# mainBoard.net
KiCad netlist of a schematic drawn in EAGLE
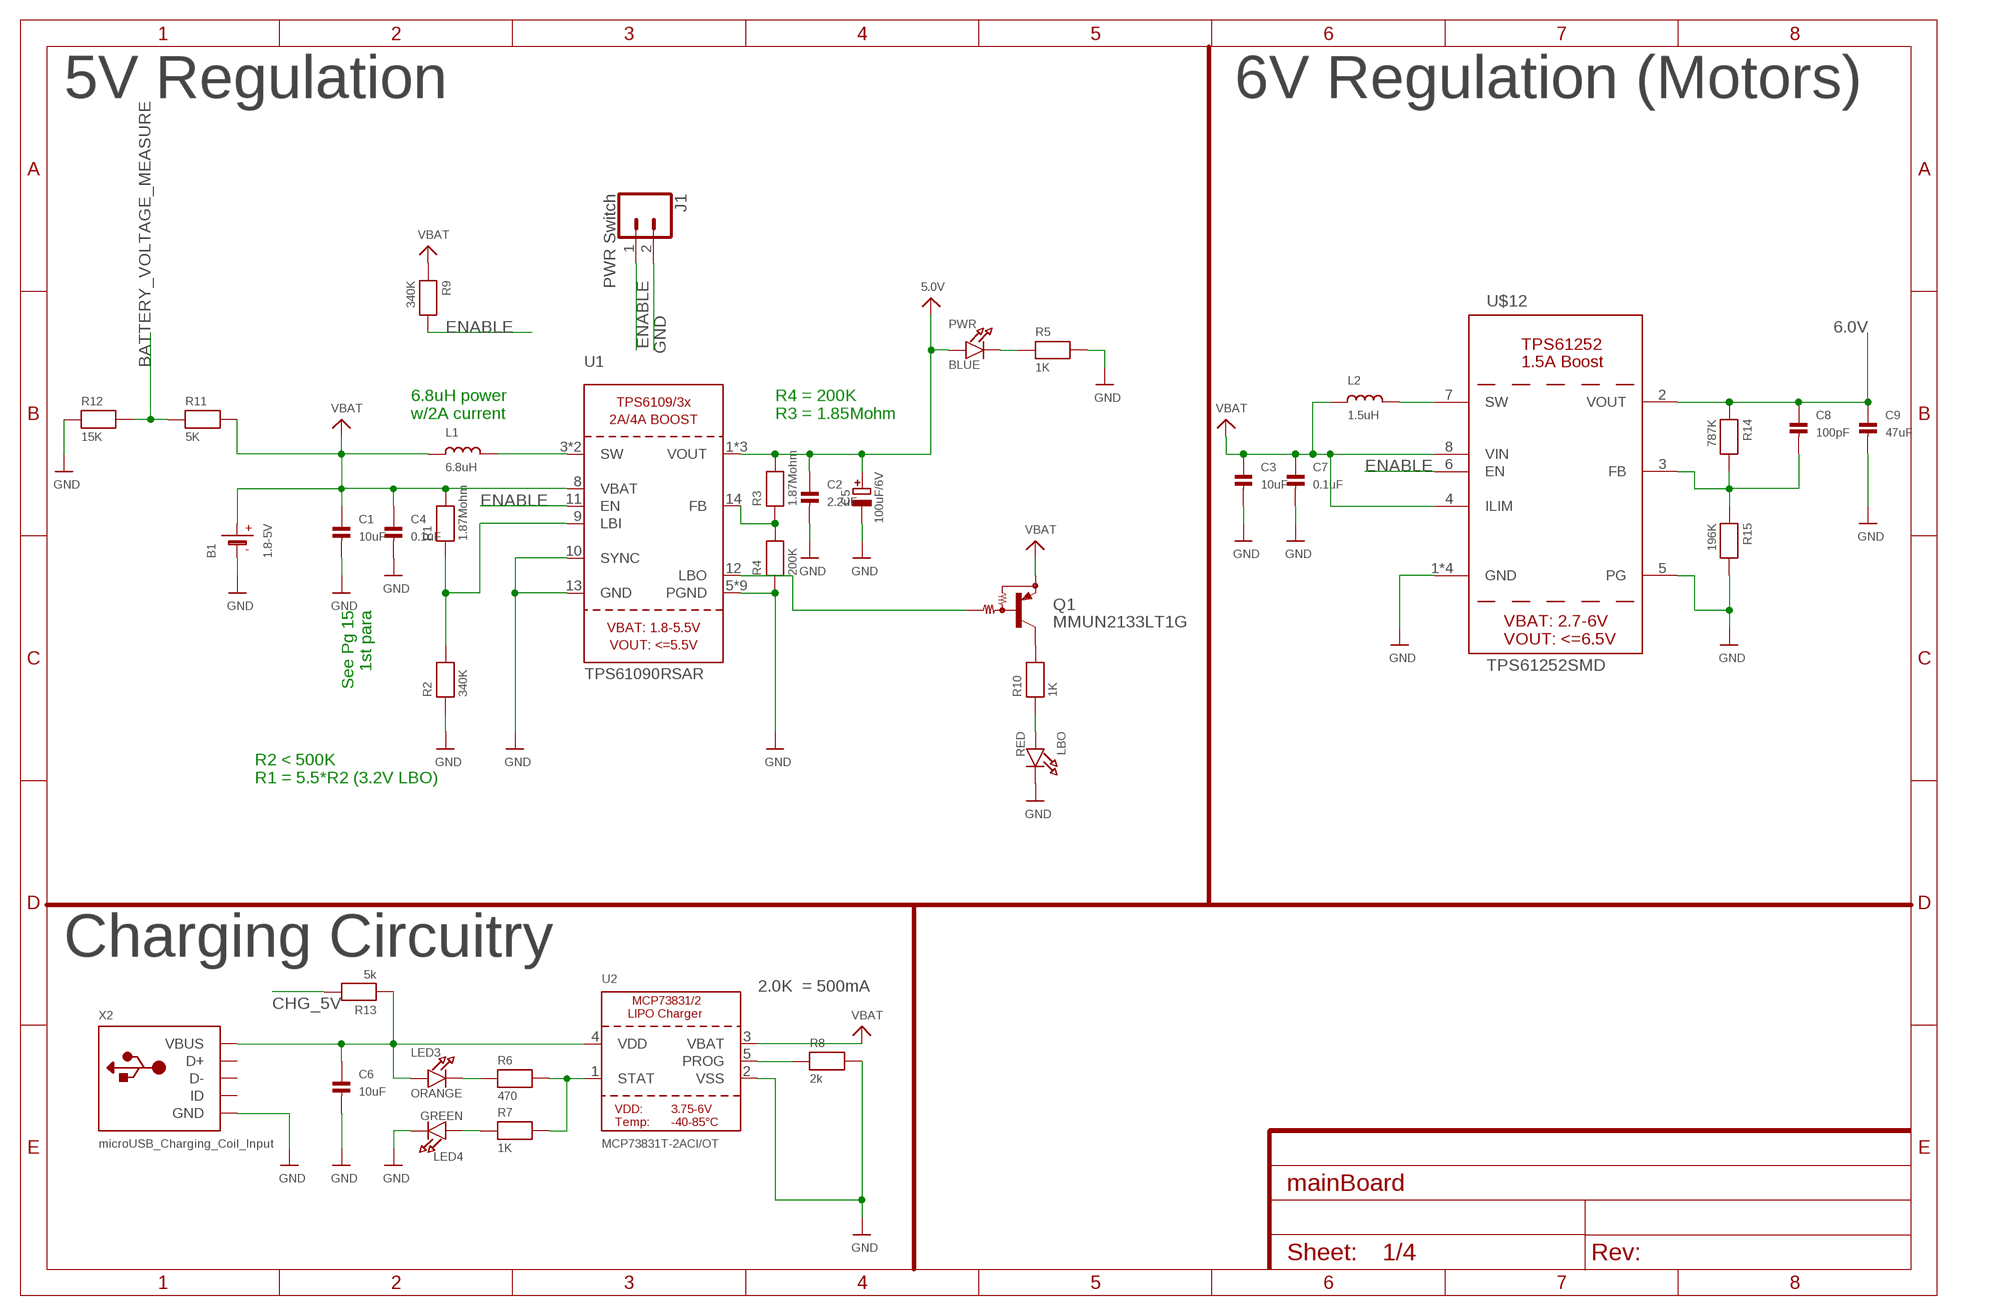
[diagram p0: schematic, sheet 1]
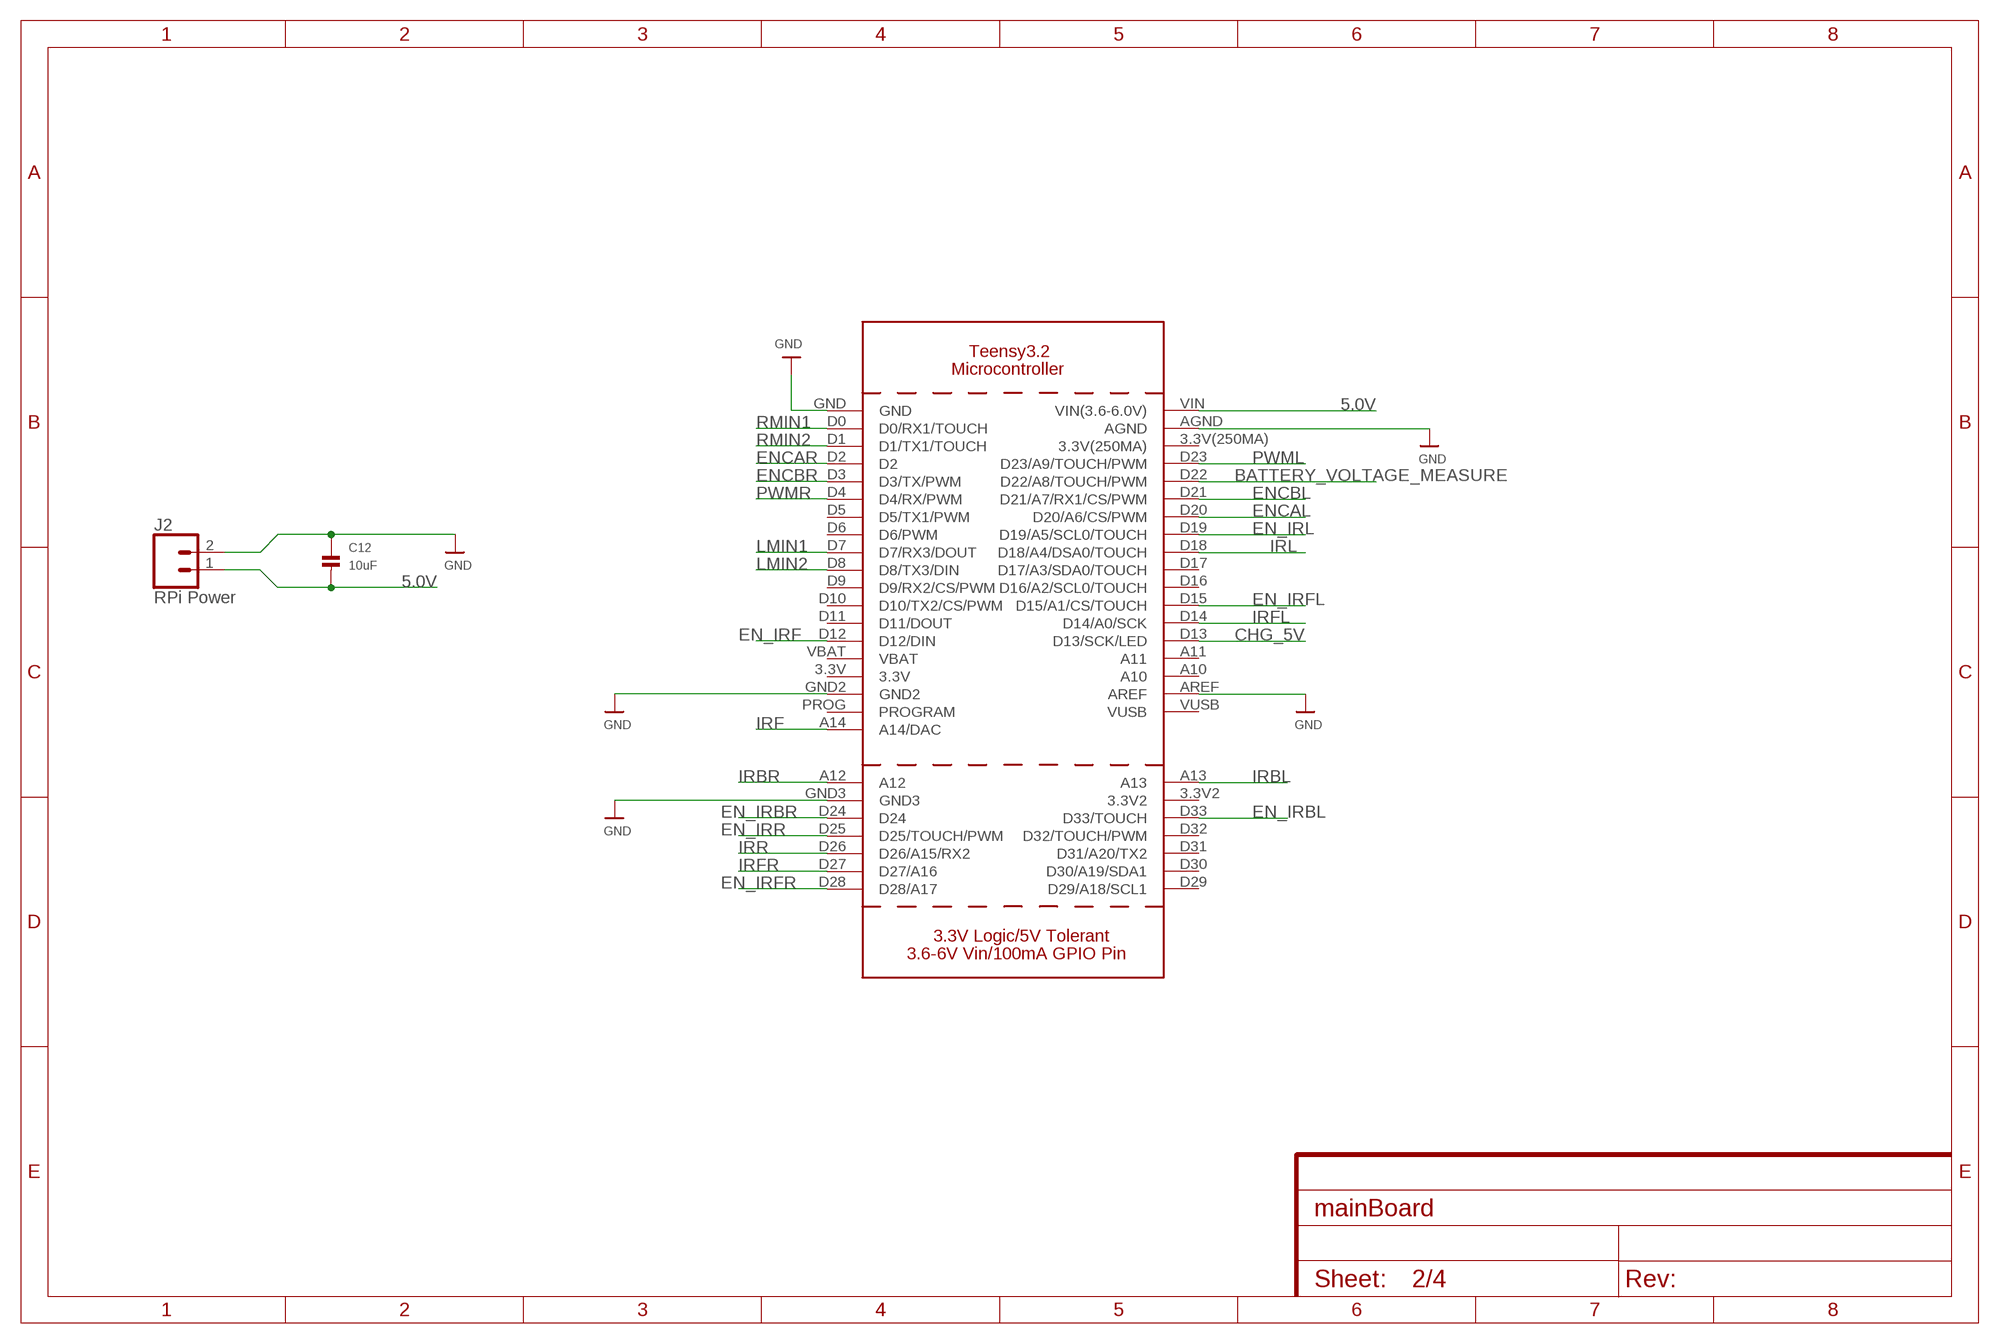
[diagram p1: schematic, sheet 2]
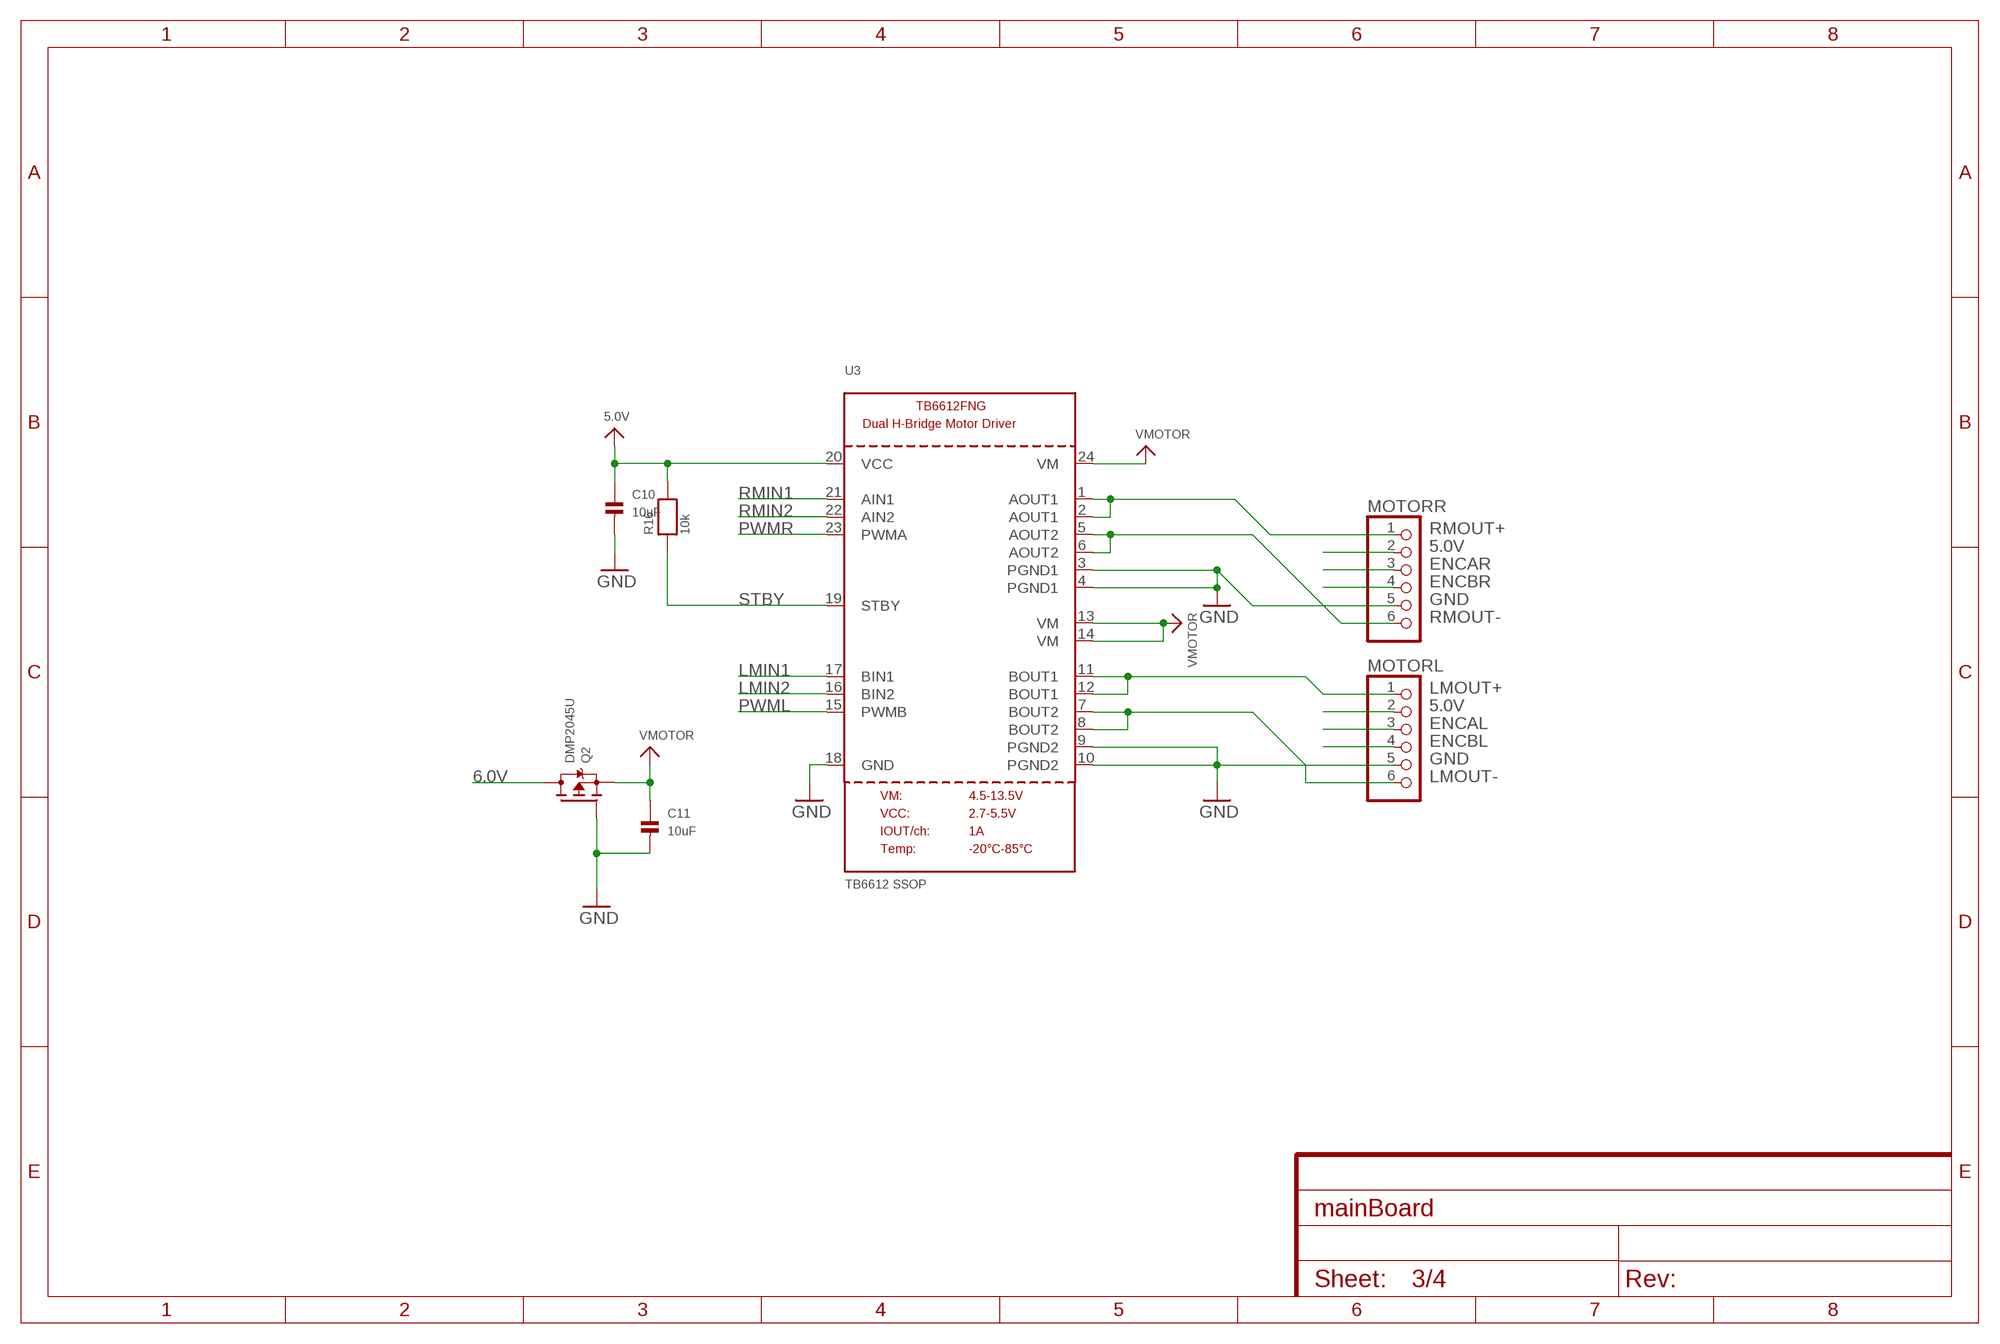
[diagram p2: schematic, sheet 3]
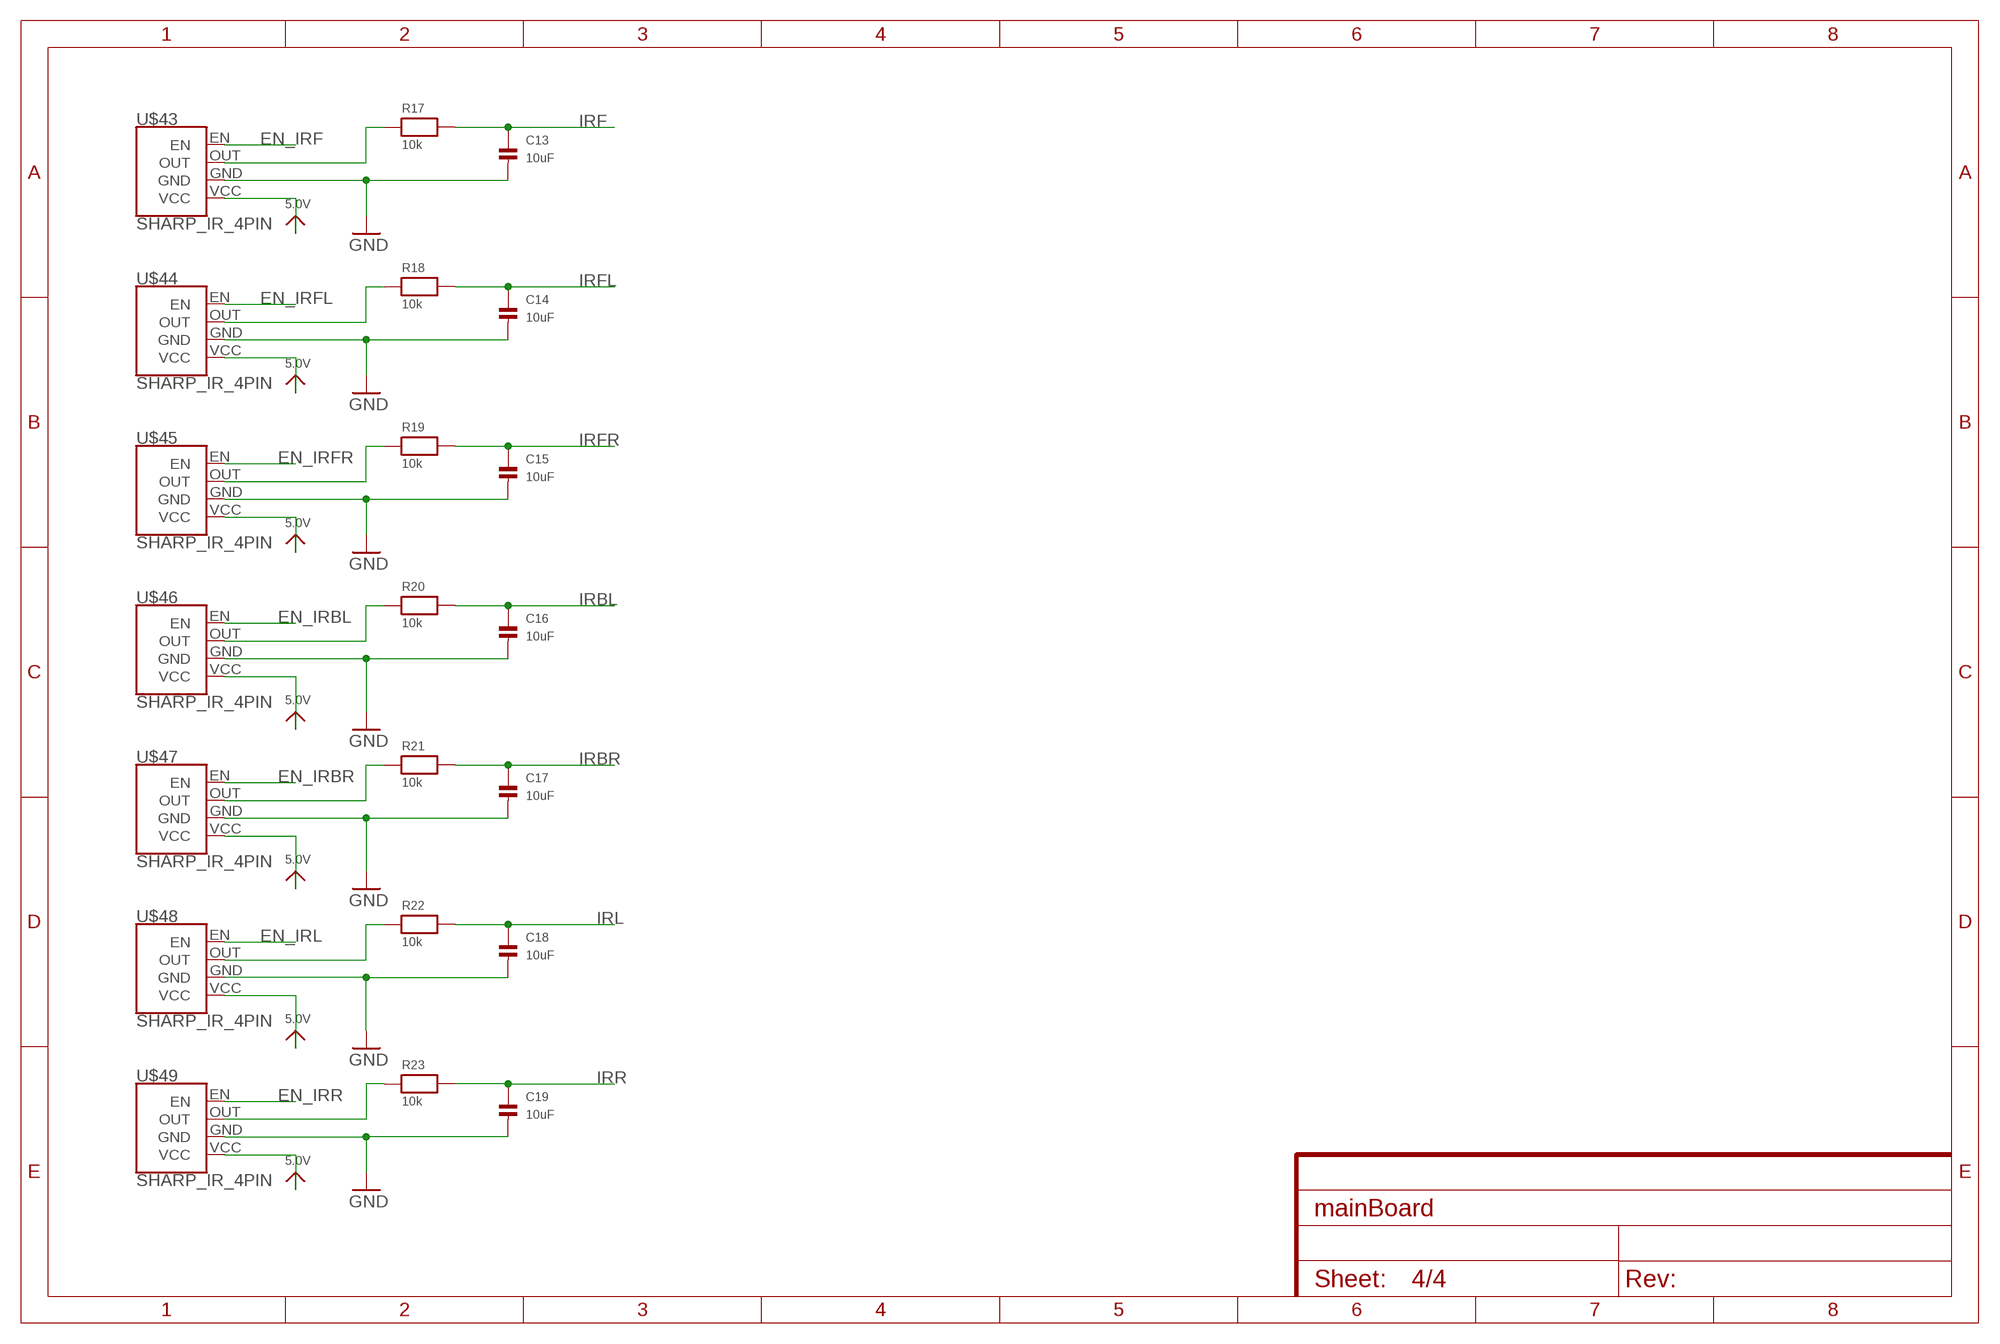
[diagram p3: schematic, sheet 4]

(export (version "E")
  (design (tool "Eeschema 10.0.6"))
  (components
    (comp (ref "C13")
      (value "10uF")
      (footprint "eagle-import:0603")
      (libsource (lib "eagle-import") (part "CAP_CERAMIC0603"))
    )
    (comp (ref "C14")
      (value "10uF")
      (footprint "eagle-import:0603")
      (libsource (lib "eagle-import") (part "CAP_CERAMIC0603"))
    )
    (comp (ref "C15")
      (value "10uF")
      (footprint "eagle-import:0603")
      (libsource (lib "eagle-import") (part "CAP_CERAMIC0603"))
    )
    (comp (ref "C16")
      (value "10uF")
      (footprint "eagle-import:0603")
      (libsource (lib "eagle-import") (part "CAP_CERAMIC0603"))
    )
    (comp (ref "C17")
      (value "10uF")
      (footprint "eagle-import:0603")
      (libsource (lib "eagle-import") (part "CAP_CERAMIC0603"))
    )
    (comp (ref "C18")
      (value "10uF")
      (footprint "eagle-import:0603")
      (libsource (lib "eagle-import") (part "CAP_CERAMIC0603"))
    )
    (comp (ref "C19")
      (value "10uF")
      (footprint "eagle-import:0603")
      (libsource (lib "eagle-import") (part "CAP_CERAMIC0603"))
    )
    (comp (ref "R17")
      (value "10k")
      (footprint "eagle-import:0805")
      (libsource (lib "eagle-import") (part "RESISTOR0805"))
    )
    (comp (ref "R18")
      (value "10k")
      (footprint "eagle-import:0805")
      (libsource (lib "eagle-import") (part "RESISTOR0805"))
    )
    (comp (ref "R19")
      (value "10k")
      (footprint "eagle-import:0805")
      (libsource (lib "eagle-import") (part "RESISTOR0805"))
    )
    (comp (ref "R20")
      (value "10k")
      (footprint "eagle-import:0805")
      (libsource (lib "eagle-import") (part "RESISTOR0805"))
    )
    (comp (ref "R21")
      (value "10k")
      (footprint "eagle-import:0805")
      (libsource (lib "eagle-import") (part "RESISTOR0805"))
    )
    (comp (ref "R22")
      (value "10k")
      (footprint "eagle-import:0805")
      (libsource (lib "eagle-import") (part "RESISTOR0805"))
    )
    (comp (ref "R23")
      (value "10k")
      (footprint "eagle-import:0805")
      (libsource (lib "eagle-import") (part "RESISTOR0805"))
    )
    (comp (ref "U$43")
      (value "SHARP_IR_4PIN")
      (footprint "eagle-import:SHARP_IR_4PIN")
      (libsource (lib "eagle-import") (part "SHARP_IR_4PIN"))
    )
    (comp (ref "U$44")
      (value "SHARP_IR_4PIN")
      (footprint "eagle-import:SHARP_IR_4PIN")
      (libsource (lib "eagle-import") (part "SHARP_IR_4PIN"))
    )
    (comp (ref "U$45")
      (value "SHARP_IR_4PIN")
      (footprint "eagle-import:SHARP_IR_4PIN")
      (libsource (lib "eagle-import") (part "SHARP_IR_4PIN"))
    )
    (comp (ref "U$46")
      (value "SHARP_IR_4PIN")
      (footprint "eagle-import:SHARP_IR_4PIN")
      (libsource (lib "eagle-import") (part "SHARP_IR_4PIN"))
    )
    (comp (ref "U$47")
      (value "SHARP_IR_4PIN")
      (footprint "eagle-import:SHARP_IR_4PIN")
      (libsource (lib "eagle-import") (part "SHARP_IR_4PIN"))
    )
    (comp (ref "U$48")
      (value "SHARP_IR_4PIN")
      (footprint "eagle-import:SHARP_IR_4PIN")
      (libsource (lib "eagle-import") (part "SHARP_IR_4PIN"))
    )
    (comp (ref "U$49")
      (value "SHARP_IR_4PIN")
      (footprint "eagle-import:SHARP_IR_4PIN")
      (libsource (lib "eagle-import") (part "SHARP_IR_4PIN"))
    )
    (comp (ref "B1")
      (value "1.8-5V")
      (footprint "eagle-import:JSTPH2")
      (libsource (lib "eagle-import") (part "BATTERY"))
    )
    (comp (ref "C1")
      (value "10uF")
      (footprint "eagle-import:0603")
      (libsource (lib "eagle-import") (part "CAP_CERAMIC0603"))
    )
    (comp (ref "C2")
      (value "2.2uF")
      (footprint "eagle-import:0603")
      (libsource (lib "eagle-import") (part "CAP_CERAMIC0603"))
    )
    (comp (ref "C3")
      (value "10uF")
      (footprint "eagle-import:0603")
      (libsource (lib "eagle-import") (part "CAP_CERAMIC0603"))
    )
    (comp (ref "C4")
      (value "0.1uF")
      (footprint "eagle-import:0805")
      (libsource (lib "eagle-import") (part "CAP_CERAMIC0805"))
    )
    (comp (ref "C5")
      (value "100uF/6V")
      (footprint "eagle-import:EIA3528-21_B-R")
      (libsource (lib "eagle-import") (part "CAP_TANTALUMB/3528_REFLOW"))
    )
    (comp (ref "C6")
      (value "10uF")
      (footprint "eagle-import:0603")
      (libsource (lib "eagle-import") (part "CAP_CERAMIC0603"))
    )
    (comp (ref "C7")
      (value "0.1uF")
      (footprint "eagle-import:0805")
      (libsource (lib "eagle-import") (part "CAP_CERAMIC0805"))
    )
    (comp (ref "C8")
      (value "100pF")
      (footprint "eagle-import:0603")
      (libsource (lib "eagle-import") (part "CAP_CERAMIC0603"))
    )
    (comp (ref "C9")
      (value "47uF")
      (footprint "eagle-import:1206")
      (libsource (lib "eagle-import") (part "CAP_CERAMIC1206"))
    )
    (comp (ref "J1")
      (value "PWR Switch")
      (footprint "eagle-import:1X02")
      (libsource (lib "eagle-import") (part "CONN_02"))
    )
    (comp (ref "L1")
      (value "6.8uH")
      (footprint "eagle-import:VISHAY_IHLP2525CZER6R8M01")
      (libsource (lib "eagle-import") (part "VISHAY_IHLP2525CZER6R8M01"))
    )
    (comp (ref "L2")
      (value "1.5uH")
      (footprint "eagle-import:MURATA_DFE252012P-1R5M=P2")
      (libsource (lib "eagle-import") (part "MURATA_DFE252012P-1R5M=P2"))
    )
    (comp (ref "LBO")
      (value "RED")
      (footprint "eagle-import:CHIPLED_0805_NOOUTLINE")
      (libsource (lib "eagle-import") (part "LED0805_NOOUTLINE"))
    )
    (comp (ref "LED3")
      (value "ORANGE")
      (footprint "eagle-import:CHIPLED_0805_NOOUTLINE")
      (libsource (lib "eagle-import") (part "LED0805_NOOUTLINE"))
    )
    (comp (ref "LED4")
      (value "GREEN")
      (footprint "eagle-import:CHIPLED_0805_NOOUTLINE")
      (libsource (lib "eagle-import") (part "LED0805_NOOUTLINE"))
    )
    (comp (ref "PWR")
      (value "BLUE")
      (footprint "eagle-import:CHIPLED_0805_NOOUTLINE")
      (libsource (lib "eagle-import") (part "LED0805_NOOUTLINE"))
    )
    (comp (ref "Q1")
      (value "MMUN2133LT1G")
      (footprint "eagle-import:SC59-BEC")
      (libsource (lib "eagle-import") (part "-PNP_DRIVER-SC59-BECMUN2114T1"))
    )
    (comp (ref "R1")
      (value "1.87Mohm")
      (footprint "eagle-import:0805")
      (libsource (lib "eagle-import") (part "RESISTOR0805"))
    )
    (comp (ref "R2")
      (value "340K")
      (footprint "eagle-import:0805")
      (libsource (lib "eagle-import") (part "RESISTOR0805"))
    )
    (comp (ref "R3")
      (value "1.87Mohm")
      (footprint "eagle-import:0805")
      (libsource (lib "eagle-import") (part "RESISTOR0805"))
    )
    (comp (ref "R4")
      (value "200K")
      (footprint "eagle-import:0805")
      (libsource (lib "eagle-import") (part "RESISTOR0805"))
    )
    (comp (ref "R5")
      (value "1K")
      (footprint "eagle-import:0805")
      (libsource (lib "eagle-import") (part "RESISTOR0805"))
    )
    (comp (ref "R6")
      (value "470")
      (footprint "eagle-import:0805")
      (libsource (lib "eagle-import") (part "RESISTOR0805"))
    )
    (comp (ref "R7")
      (value "1K")
      (footprint "eagle-import:0805")
      (libsource (lib "eagle-import") (part "RESISTOR0805"))
    )
    (comp (ref "R8")
      (value "2k")
      (footprint "eagle-import:0805")
      (libsource (lib "eagle-import") (part "RESISTOR0805"))
    )
    (comp (ref "R9")
      (value "340K")
      (footprint "eagle-import:0805")
      (libsource (lib "eagle-import") (part "RESISTOR0805"))
    )
    (comp (ref "R10")
      (value "1K")
      (footprint "eagle-import:0805")
      (libsource (lib "eagle-import") (part "RESISTOR0805"))
    )
    (comp (ref "R11")
      (value "5K")
      (footprint "eagle-import:0805")
      (libsource (lib "eagle-import") (part "RESISTOR0805"))
    )
    (comp (ref "R12")
      (value "15K")
      (footprint "eagle-import:0805")
      (libsource (lib "eagle-import") (part "RESISTOR0805"))
    )
    (comp (ref "R13")
      (value "5k")
      (footprint "eagle-import:0805")
      (libsource (lib "eagle-import") (part "RESISTOR0805"))
    )
    (comp (ref "R14")
      (value "787K")
      (footprint "eagle-import:0805")
      (libsource (lib "eagle-import") (part "RESISTOR0805"))
    )
    (comp (ref "R15")
      (value "196K")
      (footprint "eagle-import:0805")
      (libsource (lib "eagle-import") (part "RESISTOR0805"))
    )
    (comp (ref "U$12")
      (value "TPS61252SMD")
      (footprint "eagle-import:TPS61252")
      (libsource (lib "eagle-import") (part "TPS61252SMD"))
    )
    (comp (ref "U1")
      (value "TPS61090RSAR")
      (footprint "eagle-import:PVQFN-16")
      (libsource (lib "eagle-import") (part "VREG_TPS6103X"))
    )
    (comp (ref "U2")
      (value "MCP73831T-2ACI/OT")
      (footprint "eagle-import:SOT23-5")
      (libsource (lib "eagle-import") (part "MCP73831/2"))
    )
    (comp (ref "X2")
      (value "microUSB_Charging_Coil_Input")
      (footprint "eagle-import:4UCONN_20329")
      (libsource (lib "eagle-import") (part "USBMICRO_20329"))
    )
    (comp (ref "C10")
      (value "10uF")
      (footprint "eagle-import:0603")
      (libsource (lib "eagle-import") (part "CAP_CERAMIC0603"))
    )
    (comp (ref "C11")
      (value "10uF")
      (footprint "eagle-import:0603")
      (libsource (lib "eagle-import") (part "CAP_CERAMIC0603"))
    )
    (comp (ref "MOTORL")
      (value "PINHD-1X6CB")
      (footprint "eagle-import:1X06-CLEANBIG")
      (libsource (lib "eagle-import") (part "PINHD-1X6CB"))
    )
    (comp (ref "MOTORR")
      (value "PINHD-1X6CB")
      (footprint "eagle-import:1X06-CLEANBIG")
      (libsource (lib "eagle-import") (part "PINHD-1X6CB"))
    )
    (comp (ref "Q2")
      (value "DMP2045U")
      (footprint "eagle-import:SOT23-WIDE")
      (libsource (lib "eagle-import") (part "MOSFET-PWIDE"))
    )
    (comp (ref "R16")
      (value "10k")
      (footprint "eagle-import:0805")
      (libsource (lib "eagle-import") (part "RESISTOR0805"))
    )
    (comp (ref "U3")
      (value "TB6612 SSOP")
      (footprint "eagle-import:SSOP24")
      (libsource (lib "eagle-import") (part "TB6612FNGSSOP"))
    )
    (comp (ref "C12")
      (value "10uF")
      (footprint "eagle-import:0603")
      (libsource (lib "eagle-import") (part "CAP_CERAMIC0603"))
    )
    (comp (ref "J2")
      (value "RPi Power")
      (footprint "eagle-import:1X02")
      (libsource (lib "eagle-import") (part "CONN_02"))
    )
    (comp (ref "U$28")
      (value "TEENSY3_2")
      (footprint "eagle-import:TEENSY3_2")
      (libsource (lib "eagle-import") (part "TEENSY3_2"))
    )
  )
  (nets
    (net (code "1") (name "5.0V") (class "Default")
      (node (ref "C10") (pin "1") (pinfunction "P$1_1") (pintype "passive"))
      (node (ref "C12") (pin "2") (pinfunction "P$2_2") (pintype "passive"))
      (node (ref "C2") (pin "1") (pinfunction "P$1_1") (pintype "passive"))
      (node (ref "C5") (pin "+") (pinfunction "+_+") (pintype "passive"))
      (node (ref "J2") (pin "1") (pinfunction "1_1") (pintype "passive"))
      (node (ref "MOTORL") (pin "2") (pinfunction "2_2") (pintype "passive"))
      (node (ref "MOTORR") (pin "2") (pinfunction "2_2") (pintype "passive"))
      (node (ref "PWR") (pin "A") (pinfunction "A_A") (pintype "passive"))
      (node (ref "R16") (pin "2") (pinfunction "2_2") (pintype "passive"))
      (node (ref "R3") (pin "2") (pinfunction "2_2") (pintype "passive"))
      (node (ref "U$28") (pin "VIN") (pinfunction "VIN(3.6-6.0V)_VIN") (pintype "bidirectional"))
      (node (ref "U$43") (pin "VCC") (pinfunction "VCC_VCC") (pintype "bidirectional"))
      (node (ref "U$44") (pin "VCC") (pinfunction "VCC_VCC") (pintype "bidirectional"))
      (node (ref "U$45") (pin "VCC") (pinfunction "VCC_VCC") (pintype "bidirectional"))
      (node (ref "U$46") (pin "VCC") (pinfunction "VCC_VCC") (pintype "bidirectional"))
      (node (ref "U$47") (pin "VCC") (pinfunction "VCC_VCC") (pintype "bidirectional"))
      (node (ref "U$48") (pin "VCC") (pinfunction "VCC_VCC") (pintype "bidirectional"))
      (node (ref "U$49") (pin "VCC") (pinfunction "VCC_VCC") (pintype "bidirectional"))
      (node (ref "U1") (pin "1") (pinfunction "VOUT_1") (pintype "power_in"))
      (node (ref "U1") (pin "15") (pinfunction "VOUT_15") (pintype "power_in"))
      (node (ref "U1") (pin "16") (pinfunction "VOUT_16") (pintype "power_in"))
      (node (ref "U3") (pin "20") (pinfunction "VCC_20") (pintype "power_in"))
    )
    (net (code "2") (name "6.0V") (class "Default")
      (node (ref "C8") (pin "1") (pinfunction "P$1_1") (pintype "passive"))
      (node (ref "C9") (pin "1") (pinfunction "P$1_1") (pintype "passive"))
      (node (ref "Q2") (pin "3") (pinfunction "D_3") (pintype "passive"))
      (node (ref "R14") (pin "1") (pinfunction "1_1") (pintype "passive"))
      (node (ref "U$12") (pin "2") (pinfunction "VOUT_2") (pintype "bidirectional"))
    )
    (net (code "3") (name "BATTERY_VOLTAGE_MEASURE") (class "Default")
      (node (ref "R11") (pin "1") (pinfunction "1_1") (pintype "passive"))
      (node (ref "R12") (pin "2") (pinfunction "2_2") (pintype "passive"))
      (node (ref "U$28") (pin "D22") (pinfunction "D22/A8/TOUCH/PWM_D22") (pintype "bidirectional"))
    )
    (net (code "4") (name "CHG_5V") (class "Default")
      (node (ref "R13") (pin "2") (pinfunction "2_2") (pintype "passive"))
      (node (ref "U$28") (pin "D13") (pinfunction "D13/SCK/LED_D13") (pintype "bidirectional"))
    )
    (net (code "5") (name "ENABLE") (class "Default")
      (node (ref "J1") (pin "1") (pinfunction "1_1") (pintype "passive"))
      (node (ref "R9") (pin "2") (pinfunction "2_2") (pintype "passive"))
      (node (ref "U$12") (pin "6") (pinfunction "EN_6") (pintype "bidirectional"))
      (node (ref "U1") (pin "11") (pinfunction "EN_11") (pintype "input"))
    )
    (net (code "6") (name "ENCAL") (class "Default")
      (node (ref "MOTORL") (pin "3") (pinfunction "3_3") (pintype "passive"))
      (node (ref "U$28") (pin "D20") (pinfunction "D20/A6/CS/PWM_D20") (pintype "bidirectional"))
    )
    (net (code "7") (name "ENCAR") (class "Default")
      (node (ref "MOTORR") (pin "3") (pinfunction "3_3") (pintype "passive"))
      (node (ref "U$28") (pin "D2") (pinfunction "D2_D2") (pintype "bidirectional"))
    )
    (net (code "8") (name "ENCBL") (class "Default")
      (node (ref "MOTORL") (pin "4") (pinfunction "4_4") (pintype "passive"))
      (node (ref "U$28") (pin "D21") (pinfunction "D21/A7/RX1/CS/PWM_D21") (pintype "bidirectional"))
    )
    (net (code "9") (name "ENCBR") (class "Default")
      (node (ref "MOTORR") (pin "4") (pinfunction "4_4") (pintype "passive"))
      (node (ref "U$28") (pin "D3") (pinfunction "D3/TX/PWM_D3") (pintype "bidirectional"))
    )
    (net (code "10") (name "EN_IRBL") (class "Default")
      (node (ref "U$28") (pin "D33") (pinfunction "D33/TOUCH_D33") (pintype "bidirectional"))
      (node (ref "U$46") (pin "EN") (pinfunction "EN_EN") (pintype "bidirectional"))
    )
    (net (code "11") (name "EN_IRBR") (class "Default")
      (node (ref "U$28") (pin "D24") (pinfunction "D24_D24") (pintype "bidirectional"))
      (node (ref "U$47") (pin "EN") (pinfunction "EN_EN") (pintype "bidirectional"))
    )
    (net (code "12") (name "EN_IRF") (class "Default")
      (node (ref "U$28") (pin "D12") (pinfunction "D12/DIN_D12") (pintype "bidirectional"))
      (node (ref "U$43") (pin "EN") (pinfunction "EN_EN") (pintype "bidirectional"))
    )
    (net (code "13") (name "EN_IRFL") (class "Default")
      (node (ref "U$28") (pin "D15") (pinfunction "D15/A1/CS/TOUCH_D15") (pintype "bidirectional"))
      (node (ref "U$44") (pin "EN") (pinfunction "EN_EN") (pintype "bidirectional"))
    )
    (net (code "14") (name "EN_IRFR") (class "Default")
      (node (ref "U$28") (pin "D28") (pinfunction "D28/A17_D28") (pintype "bidirectional"))
      (node (ref "U$45") (pin "EN") (pinfunction "EN_EN") (pintype "bidirectional"))
    )
    (net (code "15") (name "EN_IRL") (class "Default")
      (node (ref "U$28") (pin "D19") (pinfunction "D19/A5/SCL0/TOUCH_D19") (pintype "bidirectional"))
      (node (ref "U$48") (pin "EN") (pinfunction "EN_EN") (pintype "bidirectional"))
    )
    (net (code "16") (name "EN_IRR") (class "Default")
      (node (ref "U$28") (pin "D25") (pinfunction "D25/TOUCH/PWM_D25") (pintype "bidirectional"))
      (node (ref "U$49") (pin "EN") (pinfunction "EN_EN") (pintype "bidirectional"))
    )
    (net (code "17") (name "GND") (class "Default")
      (node (ref "B1") (pin "1") (pinfunction "-_1") (pintype "passive"))
      (node (ref "C1") (pin "2") (pinfunction "P$2_2") (pintype "passive"))
      (node (ref "C10") (pin "2") (pinfunction "P$2_2") (pintype "passive"))
      (node (ref "C11") (pin "2") (pinfunction "P$2_2") (pintype "passive"))
      (node (ref "C12") (pin "1") (pinfunction "P$1_1") (pintype "passive"))
      (node (ref "C13") (pin "2") (pinfunction "P$2_2") (pintype "passive"))
      (node (ref "C14") (pin "2") (pinfunction "P$2_2") (pintype "passive"))
      (node (ref "C15") (pin "2") (pinfunction "P$2_2") (pintype "passive"))
      (node (ref "C16") (pin "2") (pinfunction "P$2_2") (pintype "passive"))
      (node (ref "C17") (pin "2") (pinfunction "P$2_2") (pintype "passive"))
      (node (ref "C18") (pin "2") (pinfunction "P$2_2") (pintype "passive"))
      (node (ref "C19") (pin "2") (pinfunction "P$2_2") (pintype "passive"))
      (node (ref "C2") (pin "2") (pinfunction "P$2_2") (pintype "passive"))
      (node (ref "C3") (pin "2") (pinfunction "P$2_2") (pintype "passive"))
      (node (ref "C4") (pin "2") (pinfunction "P$2_2") (pintype "passive"))
      (node (ref "C5") (pin "-") (pinfunction "-_-") (pintype "passive"))
      (node (ref "C6") (pin "2") (pinfunction "P$2_2") (pintype "passive"))
      (node (ref "C7") (pin "2") (pinfunction "P$2_2") (pintype "passive"))
      (node (ref "C9") (pin "2") (pinfunction "P$2_2") (pintype "passive"))
      (node (ref "J1") (pin "2") (pinfunction "2_2") (pintype "passive"))
      (node (ref "J2") (pin "2") (pinfunction "2_2") (pintype "passive"))
      (node (ref "LBO") (pin "C") (pinfunction "C_C") (pintype "passive"))
      (node (ref "LED4") (pin "C") (pinfunction "C_C") (pintype "passive"))
      (node (ref "MOTORL") (pin "5") (pinfunction "5_5") (pintype "passive"))
      (node (ref "MOTORR") (pin "5") (pinfunction "5_5") (pintype "passive"))
      (node (ref "Q2") (pin "1") (pinfunction "G_1") (pintype "passive"))
      (node (ref "R12") (pin "1") (pinfunction "1_1") (pintype "passive"))
      (node (ref "R15") (pin "2") (pinfunction "2_2") (pintype "passive"))
      (node (ref "R2") (pin "1") (pinfunction "1_1") (pintype "passive"))
      (node (ref "R4") (pin "1") (pinfunction "1_1") (pintype "passive"))
      (node (ref "R5") (pin "2") (pinfunction "2_2") (pintype "passive"))
      (node (ref "R8") (pin "2") (pinfunction "2_2") (pintype "passive"))
      (node (ref "U$12") (pin "1") (pinfunction "GND_1") (pintype "bidirectional"))
      (node (ref "U$12") (pin "5") (pinfunction "PG_5") (pintype "bidirectional"))
      (node (ref "U$12") (pin "P$2_GND") (pinfunction "GND_P$2_GND") (pintype "bidirectional"))
      (node (ref "U$12") (pin "P$3_GND") (pinfunction "GND_P$3_GND") (pintype "bidirectional"))
      (node (ref "U$12") (pin "THERMAL_GND") (pinfunction "GND_THERMAL_GND") (pintype "bidirectional"))
      (node (ref "U$28") (pin "AGND") (pinfunction "AGND_AGND") (pintype "bidirectional"))
      (node (ref "U$28") (pin "AREF") (pinfunction "AREF_AREF") (pintype "bidirectional"))
      (node (ref "U$28") (pin "GND") (pinfunction "GND_GND") (pintype "bidirectional"))
      (node (ref "U$28") (pin "GND2") (pinfunction "GND2_GND2") (pintype "bidirectional"))
      (node (ref "U$28") (pin "GND3") (pinfunction "GND3_GND3") (pintype "bidirectional"))
      (node (ref "U$43") (pin "GND") (pinfunction "GND_GND") (pintype "bidirectional"))
      (node (ref "U$44") (pin "GND") (pinfunction "GND_GND") (pintype "bidirectional"))
      (node (ref "U$45") (pin "GND") (pinfunction "GND_GND") (pintype "bidirectional"))
      (node (ref "U$46") (pin "GND") (pinfunction "GND_GND") (pintype "bidirectional"))
      (node (ref "U$47") (pin "GND") (pinfunction "GND_GND") (pintype "bidirectional"))
      (node (ref "U$48") (pin "GND") (pinfunction "GND_GND") (pintype "bidirectional"))
      (node (ref "U$49") (pin "GND") (pinfunction "GND_GND") (pintype "bidirectional"))
      (node (ref "U1") (pin "10") (pinfunction "SYNC_10") (pintype "input"))
      (node (ref "U1") (pin "13") (pinfunction "GND_13") (pintype "power_in"))
      (node (ref "U1") (pin "5") (pinfunction "PGND_5") (pintype "power_in"))
      (node (ref "U1") (pin "6") (pinfunction "PGND_6") (pintype "power_in"))
      (node (ref "U1") (pin "7") (pinfunction "PGND_7") (pintype "power_in"))
      (node (ref "U1") (pin "P$18") (pinfunction "PGND_P$18") (pintype "power_in"))
      (node (ref "U1") (pin "P$19") (pinfunction "PGND_P$19") (pintype "power_in"))
      (node (ref "U1") (pin "P$20") (pinfunction "PGND_P$20") (pintype "power_in"))
      (node (ref "U1") (pin "P$21") (pinfunction "PGND_P$21") (pintype "power_in"))
      (node (ref "U1") (pin "P$22") (pinfunction "PGND_P$22") (pintype "power_in"))
      (node (ref "U1") (pin "THERMAL") (pinfunction "PGND_THERMAL") (pintype "power_in"))
      (node (ref "U2") (pin "2") (pinfunction "VSS_2") (pintype "power_in"))
      (node (ref "U3") (pin "10") (pinfunction "PGND2_10") (pintype "power_in"))
      (node (ref "U3") (pin "18") (pinfunction "GND_18") (pintype "power_in"))
      (node (ref "U3") (pin "3") (pinfunction "PGND1_3") (pintype "power_in"))
      (node (ref "U3") (pin "4") (pinfunction "PGND1_4") (pintype "power_in"))
      (node (ref "U3") (pin "9") (pinfunction "PGND2_9") (pintype "power_in"))
      (node (ref "X2") (pin "BASE@1") (pinfunction "GND_BASE@1") (pintype "power_in"))
      (node (ref "X2") (pin "BASE@2") (pinfunction "GND_BASE@2") (pintype "power_in"))
      (node (ref "X2") (pin "GND") (pinfunction "GND_GND") (pintype "power_in"))
      (node (ref "X2") (pin "SPRT@1") (pinfunction "GND_SPRT@1") (pintype "power_in"))
      (node (ref "X2") (pin "SPRT@2") (pinfunction "GND_SPRT@2") (pintype "power_in"))
      (node (ref "X2") (pin "SPRT@3") (pinfunction "GND_SPRT@3") (pintype "power_in"))
      (node (ref "X2") (pin "SPRT@4") (pinfunction "GND_SPRT@4") (pintype "power_in"))
    )
    (net (code "18") (name "IRBL") (class "Default")
      (node (ref "C16") (pin "1") (pinfunction "P$1_1") (pintype "passive"))
      (node (ref "R20") (pin "2") (pinfunction "2_2") (pintype "passive"))
      (node (ref "U$28") (pin "A13") (pinfunction "A13_A13") (pintype "bidirectional"))
    )
    (net (code "19") (name "IRBR") (class "Default")
      (node (ref "C17") (pin "1") (pinfunction "P$1_1") (pintype "passive"))
      (node (ref "R21") (pin "2") (pinfunction "2_2") (pintype "passive"))
      (node (ref "U$28") (pin "A12") (pinfunction "A12_A12") (pintype "bidirectional"))
    )
    (net (code "20") (name "IRF") (class "Default")
      (node (ref "C13") (pin "1") (pinfunction "P$1_1") (pintype "passive"))
      (node (ref "R17") (pin "2") (pinfunction "2_2") (pintype "passive"))
      (node (ref "U$28") (pin "A14") (pinfunction "A14/DAC_A14") (pintype "bidirectional"))
    )
    (net (code "21") (name "IRFL") (class "Default")
      (node (ref "C14") (pin "1") (pinfunction "P$1_1") (pintype "passive"))
      (node (ref "R18") (pin "2") (pinfunction "2_2") (pintype "passive"))
      (node (ref "U$28") (pin "D14") (pinfunction "D14/A0/SCK_D14") (pintype "bidirectional"))
    )
    (net (code "22") (name "IRFR") (class "Default")
      (node (ref "C15") (pin "1") (pinfunction "P$1_1") (pintype "passive"))
      (node (ref "R19") (pin "2") (pinfunction "2_2") (pintype "passive"))
      (node (ref "U$28") (pin "D27") (pinfunction "D27/A16_D27") (pintype "bidirectional"))
    )
    (net (code "23") (name "IRL") (class "Default")
      (node (ref "C18") (pin "1") (pinfunction "P$1_1") (pintype "passive"))
      (node (ref "R22") (pin "2") (pinfunction "2_2") (pintype "passive"))
      (node (ref "U$28") (pin "D18") (pinfunction "D18/A4/DSA0/TOUCH_D18") (pintype "bidirectional"))
    )
    (net (code "24") (name "IRR") (class "Default")
      (node (ref "C19") (pin "1") (pinfunction "P$1_1") (pintype "passive"))
      (node (ref "R23") (pin "2") (pinfunction "2_2") (pintype "passive"))
      (node (ref "U$28") (pin "D26") (pinfunction "D26/A15/RX2_D26") (pintype "bidirectional"))
    )
    (net (code "25") (name "LMIN1") (class "Default")
      (node (ref "U$28") (pin "D7") (pinfunction "D7/RX3/DOUT_D7") (pintype "bidirectional"))
      (node (ref "U3") (pin "17") (pinfunction "BIN1_17") (pintype "input"))
    )
    (net (code "26") (name "LMIN2") (class "Default")
      (node (ref "U$28") (pin "D8") (pinfunction "D8/TX3/DIN_D8") (pintype "bidirectional"))
      (node (ref "U3") (pin "16") (pinfunction "BIN2_16") (pintype "input"))
    )
    (net (code "27") (name "LMOUT+") (class "Default")
      (node (ref "MOTORL") (pin "1") (pinfunction "1_1") (pintype "passive"))
      (node (ref "U3") (pin "11") (pinfunction "BOUT1_11") (pintype "output"))
      (node (ref "U3") (pin "12") (pinfunction "BOUT1_12") (pintype "output"))
    )
    (net (code "28") (name "LMOUT-") (class "Default")
      (node (ref "MOTORL") (pin "6") (pinfunction "6_6") (pintype "passive"))
      (node (ref "U3") (pin "7") (pinfunction "BOUT2_7") (pintype "output"))
      (node (ref "U3") (pin "8") (pinfunction "BOUT2_8") (pintype "output"))
    )
    (net (code "29") (name "Net-(C6-P$1)") (class "Default")
      (node (ref "C6") (pin "1") (pinfunction "P$1_1") (pintype "passive"))
      (node (ref "LED3") (pin "A") (pinfunction "A_A") (pintype "passive"))
      (node (ref "R13") (pin "1") (pinfunction "1_1") (pintype "passive"))
      (node (ref "U2") (pin "4") (pinfunction "VDD_4") (pintype "power_in"))
      (node (ref "X2") (pin "VBUS") (pinfunction "VBUS_VBUS") (pintype "power_in"))
    )
    (net (code "30") (name "Net-(C8-P$2)") (class "Default")
      (node (ref "C8") (pin "2") (pinfunction "P$2_2") (pintype "passive"))
      (node (ref "R14") (pin "2") (pinfunction "2_2") (pintype "passive"))
      (node (ref "R15") (pin "1") (pinfunction "1_1") (pintype "passive"))
      (node (ref "U$12") (pin "3") (pinfunction "FB_3") (pintype "bidirectional"))
    )
    (net (code "31") (name "Net-(L1-2)") (class "Default")
      (node (ref "L1") (pin "P$2") (pinfunction "2_P$2") (pintype "passive"))
      (node (ref "U1") (pin "3") (pinfunction "SW_3") (pintype "input"))
      (node (ref "U1") (pin "4") (pinfunction "SW_4") (pintype "input"))
    )
    (net (code "32") (name "Net-(L2-2)") (class "Default")
      (node (ref "L2") (pin "P$2") (pinfunction "2_P$2") (pintype "passive"))
      (node (ref "U$12") (pin "7") (pinfunction "SW_7") (pintype "bidirectional"))
    )
    (net (code "33") (name "Net-(LBO-PadA)") (class "Default")
      (node (ref "LBO") (pin "A") (pinfunction "A_A") (pintype "passive"))
      (node (ref "R10") (pin "1") (pinfunction "1_1") (pintype "passive"))
    )
    (net (code "34") (name "Net-(LED3-PadC)") (class "Default")
      (node (ref "LED3") (pin "C") (pinfunction "C_C") (pintype "passive"))
      (node (ref "R6") (pin "1") (pinfunction "1_1") (pintype "passive"))
    )
    (net (code "35") (name "Net-(LED4-PadA)") (class "Default")
      (node (ref "LED4") (pin "A") (pinfunction "A_A") (pintype "passive"))
      (node (ref "R7") (pin "1") (pinfunction "1_1") (pintype "passive"))
    )
    (net (code "36") (name "Net-(PWR-PadC)") (class "Default")
      (node (ref "PWR") (pin "C") (pinfunction "C_C") (pintype "passive"))
      (node (ref "R5") (pin "1") (pinfunction "1_1") (pintype "passive"))
    )
    (net (code "37") (name "Net-(Q1-PadC)") (class "Default")
      (node (ref "Q1") (pin "C") (pinfunction "C_C") (pintype "passive"))
      (node (ref "R10") (pin "2") (pinfunction "2_2") (pintype "passive"))
    )
    (net (code "38") (name "Net-(R17-Pad1)") (class "Default")
      (node (ref "R17") (pin "1") (pinfunction "1_1") (pintype "passive"))
      (node (ref "U$43") (pin "OUT") (pinfunction "OUT_OUT") (pintype "bidirectional"))
    )
    (net (code "39") (name "Net-(R18-Pad1)") (class "Default")
      (node (ref "R18") (pin "1") (pinfunction "1_1") (pintype "passive"))
      (node (ref "U$44") (pin "OUT") (pinfunction "OUT_OUT") (pintype "bidirectional"))
    )
    (net (code "40") (name "Net-(R19-Pad1)") (class "Default")
      (node (ref "R19") (pin "1") (pinfunction "1_1") (pintype "passive"))
      (node (ref "U$45") (pin "OUT") (pinfunction "OUT_OUT") (pintype "bidirectional"))
    )
    (net (code "41") (name "Net-(R20-Pad1)") (class "Default")
      (node (ref "R20") (pin "1") (pinfunction "1_1") (pintype "passive"))
      (node (ref "U$46") (pin "OUT") (pinfunction "OUT_OUT") (pintype "bidirectional"))
    )
    (net (code "42") (name "Net-(R21-Pad1)") (class "Default")
      (node (ref "R21") (pin "1") (pinfunction "1_1") (pintype "passive"))
      (node (ref "U$47") (pin "OUT") (pinfunction "OUT_OUT") (pintype "bidirectional"))
    )
    (net (code "43") (name "Net-(R22-Pad1)") (class "Default")
      (node (ref "R22") (pin "1") (pinfunction "1_1") (pintype "passive"))
      (node (ref "U$48") (pin "OUT") (pinfunction "OUT_OUT") (pintype "bidirectional"))
    )
    (net (code "44") (name "Net-(R23-Pad1)") (class "Default")
      (node (ref "R23") (pin "1") (pinfunction "1_1") (pintype "passive"))
      (node (ref "U$49") (pin "OUT") (pinfunction "OUT_OUT") (pintype "bidirectional"))
    )
    (net (code "45") (name "Net-(U1-FB)") (class "Default")
      (node (ref "R3") (pin "1") (pinfunction "1_1") (pintype "passive"))
      (node (ref "R4") (pin "2") (pinfunction "2_2") (pintype "passive"))
      (node (ref "U1") (pin "14") (pinfunction "FB_14") (pintype "input"))
    )
    (net (code "46") (name "Net-(U1-LBI)") (class "Default")
      (node (ref "R1") (pin "1") (pinfunction "1_1") (pintype "passive"))
      (node (ref "R2") (pin "2") (pinfunction "2_2") (pintype "passive"))
      (node (ref "U1") (pin "9") (pinfunction "LBI_9") (pintype "input"))
    )
    (net (code "47") (name "Net-(U1-LBO)") (class "Default")
      (node (ref "Q1") (pin "B") (pinfunction "B_B") (pintype "passive"))
      (node (ref "U1") (pin "12") (pinfunction "LBO_12") (pintype "output"))
    )
    (net (code "48") (name "Net-(U2-PROG)") (class "Default")
      (node (ref "R8") (pin "1") (pinfunction "1_1") (pintype "passive"))
      (node (ref "U2") (pin "5") (pinfunction "PROG_5") (pintype "input"))
    )
    (net (code "49") (name "Net-(U2-STAT)") (class "Default")
      (node (ref "R6") (pin "2") (pinfunction "2_2") (pintype "passive"))
      (node (ref "R7") (pin "2") (pinfunction "2_2") (pintype "passive"))
      (node (ref "U2") (pin "1") (pinfunction "STAT_1") (pintype "output"))
    )
    (net (code "50") (name "PWML") (class "Default")
      (node (ref "U$28") (pin "D23") (pinfunction "D23/A9/TOUCH/PWM_D23") (pintype "bidirectional"))
      (node (ref "U3") (pin "15") (pinfunction "PWMB_15") (pintype "input"))
    )
    (net (code "51") (name "PWMR") (class "Default")
      (node (ref "U$28") (pin "D4") (pinfunction "D4/RX/PWM_D4") (pintype "bidirectional"))
      (node (ref "U3") (pin "23") (pinfunction "PWMA_23") (pintype "input"))
    )
    (net (code "52") (name "RMIN1") (class "Default")
      (node (ref "U$28") (pin "D0") (pinfunction "D0/RX1/TOUCH_D0") (pintype "bidirectional"))
      (node (ref "U3") (pin "21") (pinfunction "AIN1_21") (pintype "input"))
    )
    (net (code "53") (name "RMIN2") (class "Default")
      (node (ref "U$28") (pin "D1") (pinfunction "D1/TX1/TOUCH_D1") (pintype "bidirectional"))
      (node (ref "U3") (pin "22") (pinfunction "AIN2_22") (pintype "input"))
    )
    (net (code "54") (name "RMOUT+") (class "Default")
      (node (ref "MOTORR") (pin "1") (pinfunction "1_1") (pintype "passive"))
      (node (ref "U3") (pin "1") (pinfunction "AOUT1_1") (pintype "output"))
      (node (ref "U3") (pin "2") (pinfunction "AOUT1_2") (pintype "output"))
    )
    (net (code "55") (name "RMOUT-") (class "Default")
      (node (ref "MOTORR") (pin "6") (pinfunction "6_6") (pintype "passive"))
      (node (ref "U3") (pin "5") (pinfunction "AOUT2_5") (pintype "output"))
      (node (ref "U3") (pin "6") (pinfunction "AOUT2_6") (pintype "output"))
    )
    (net (code "56") (name "STBY") (class "Default")
      (node (ref "R16") (pin "1") (pinfunction "1_1") (pintype "passive"))
      (node (ref "U3") (pin "19") (pinfunction "STBY_19") (pintype "input"))
    )
    (net (code "57") (name "VBAT") (class "Default")
      (node (ref "B1") (pin "2") (pinfunction "+_2") (pintype "passive"))
      (node (ref "C1") (pin "1") (pinfunction "P$1_1") (pintype "passive"))
      (node (ref "C3") (pin "1") (pinfunction "P$1_1") (pintype "passive"))
      (node (ref "C4") (pin "1") (pinfunction "P$1_1") (pintype "passive"))
      (node (ref "C7") (pin "1") (pinfunction "P$1_1") (pintype "passive"))
      (node (ref "L1") (pin "P$1") (pinfunction "1_P$1") (pintype "passive"))
      (node (ref "L2") (pin "P$1") (pinfunction "1_P$1") (pintype "passive"))
      (node (ref "Q1") (pin "E") (pinfunction "E_E") (pintype "passive"))
      (node (ref "R1") (pin "2") (pinfunction "2_2") (pintype "passive"))
      (node (ref "R11") (pin "2") (pinfunction "2_2") (pintype "passive"))
      (node (ref "R9") (pin "1") (pinfunction "1_1") (pintype "passive"))
      (node (ref "U$12") (pin "4") (pinfunction "ILIM_4") (pintype "bidirectional"))
      (node (ref "U$12") (pin "8") (pinfunction "VIN_8") (pintype "bidirectional"))
      (node (ref "U1") (pin "8") (pinfunction "VBAT_8") (pintype "input"))
      (node (ref "U2") (pin "3") (pinfunction "VBAT_3") (pintype "power_in"))
    )
    (net (code "58") (name "VMOTOR") (class "Default")
      (node (ref "C11") (pin "1") (pinfunction "P$1_1") (pintype "passive"))
      (node (ref "Q2") (pin "2") (pinfunction "S_2") (pintype "passive"))
      (node (ref "U3") (pin "13") (pinfunction "VM_13") (pintype "power_in"))
      (node (ref "U3") (pin "14") (pinfunction "VM_14") (pintype "power_in"))
      (node (ref "U3") (pin "24") (pinfunction "VM_24") (pintype "power_in"))
    )
    (net (code "59") (name "unconnected-(U$28-D5{slash}TX1{slash}PWM-PadD5)") (class "Default")
      (node (ref "U$28") (pin "D5") (pinfunction "D5/TX1/PWM_D5") (pintype "bidirectional"))
    )
    (net (code "60") (name "unconnected-(U$28-D6{slash}PWM-PadD6)") (class "Default")
      (node (ref "U$28") (pin "D6") (pinfunction "D6/PWM_D6") (pintype "bidirectional"))
    )
    (net (code "61") (name "unconnected-(U$28-D9{slash}RX2{slash}CS{slash}PWM-PadD9)") (class "Default")
      (node (ref "U$28") (pin "D9") (pinfunction "D9/RX2/CS/PWM_D9") (pintype "bidirectional"))
    )
    (net (code "62") (name "unconnected-(U$28-D10{slash}TX2{slash}CS{slash}PWM-PadD10)") (class "Default")
      (node (ref "U$28") (pin "D10") (pinfunction "D10/TX2/CS/PWM_D10") (pintype "bidirectional"))
    )
    (net (code "63") (name "unconnected-(U$28-D11{slash}DOUT-PadD11)") (class "Default")
      (node (ref "U$28") (pin "D11") (pinfunction "D11/DOUT_D11") (pintype "bidirectional"))
    )
    (net (code "64") (name "unconnected-(U$28-D16{slash}A2{slash}SCL0{slash}TOUCH-PadD16)") (class "Default")
      (node (ref "U$28") (pin "D16") (pinfunction "D16/A2/SCL0/TOUCH_D16") (pintype "bidirectional"))
    )
    (net (code "65") (name "unconnected-(U$28-D17{slash}A3{slash}SDA0{slash}TOUCH-PadD17)") (class "Default")
      (node (ref "U$28") (pin "D17") (pinfunction "D17/A3/SDA0/TOUCH_D17") (pintype "bidirectional"))
    )
    (net (code "66") (name "unconnected-(U$28-D29{slash}A18{slash}SCL1-PadD29)") (class "Default")
      (node (ref "U$28") (pin "D29") (pinfunction "D29/A18/SCL1_D29") (pintype "bidirectional"))
    )
    (net (code "67") (name "unconnected-(U$28-D30{slash}A19{slash}SDA1-PadD30)") (class "Default")
      (node (ref "U$28") (pin "D30") (pinfunction "D30/A19/SDA1_D30") (pintype "bidirectional"))
    )
    (net (code "68") (name "unconnected-(U$28-D31{slash}A20{slash}TX2-PadD31)") (class "Default")
      (node (ref "U$28") (pin "D31") (pinfunction "D31/A20/TX2_D31") (pintype "bidirectional"))
    )
    (net (code "69") (name "unconnected-(U$28-D32{slash}TOUCH{slash}PWM-PadD32)") (class "Default")
      (node (ref "U$28") (pin "D32") (pinfunction "D32/TOUCH/PWM_D32") (pintype "bidirectional"))
    )
    (net (code "70") (name "unconnected-(U$28-PROGRAM-PadPROG)") (class "Default")
      (node (ref "U$28") (pin "PROG") (pinfunction "PROGRAM_PROG") (pintype "bidirectional"))
    )
    (net (code "71") (name "unconnected-(U$28-Pad3.3V(250MA))") (class "Default")
      (node (ref "U$28") (pin "3.3V(250MA)") (pinfunction "3.3V(250MA)_3.3V(250MA)") (pintype "bidirectional"))
    )
    (net (code "72") (name "unconnected-(U$28-Pad3.3V)") (class "Default")
      (node (ref "U$28") (pin "3.3V") (pinfunction "3.3V_3.3V") (pintype "bidirectional"))
    )
    (net (code "73") (name "unconnected-(U$28-Pad3.3V2)") (class "Default")
      (node (ref "U$28") (pin "3.3V2") (pinfunction "3.3V2_3.3V2") (pintype "bidirectional"))
    )
    (net (code "74") (name "unconnected-(U$28-PadA10)") (class "Default")
      (node (ref "U$28") (pin "A10") (pinfunction "A10_A10") (pintype "bidirectional"))
    )
    (net (code "75") (name "unconnected-(U$28-PadA11)") (class "Default")
      (node (ref "U$28") (pin "A11") (pinfunction "A11_A11") (pintype "bidirectional"))
    )
    (net (code "76") (name "unconnected-(U$28-PadVBAT)") (class "Default")
      (node (ref "U$28") (pin "VBAT") (pinfunction "VBAT_VBAT") (pintype "bidirectional"))
    )
    (net (code "77") (name "unconnected-(U$28-PadVUSB)") (class "Default")
      (node (ref "U$28") (pin "VUSB") (pinfunction "VUSB_VUSB") (pintype "bidirectional"))
    )
    (net (code "78") (name "unconnected-(X2-PadD+)") (class "Default")
      (node (ref "X2") (pin "D+") (pinfunction "D+_D+") (pintype "bidirectional"))
    )
    (net (code "79") (name "unconnected-(X2-PadD-)") (class "Default")
      (node (ref "X2") (pin "D-") (pinfunction "D-_D-") (pintype "bidirectional"))
    )
    (net (code "80") (name "unconnected-(X2-PadID)") (class "Default")
      (node (ref "X2") (pin "ID") (pinfunction "ID_ID") (pintype "bidirectional"))
    )
  )
)
